# FPGA_Bank.net
KiCad netlist of a schematic drawn in Altium Designer
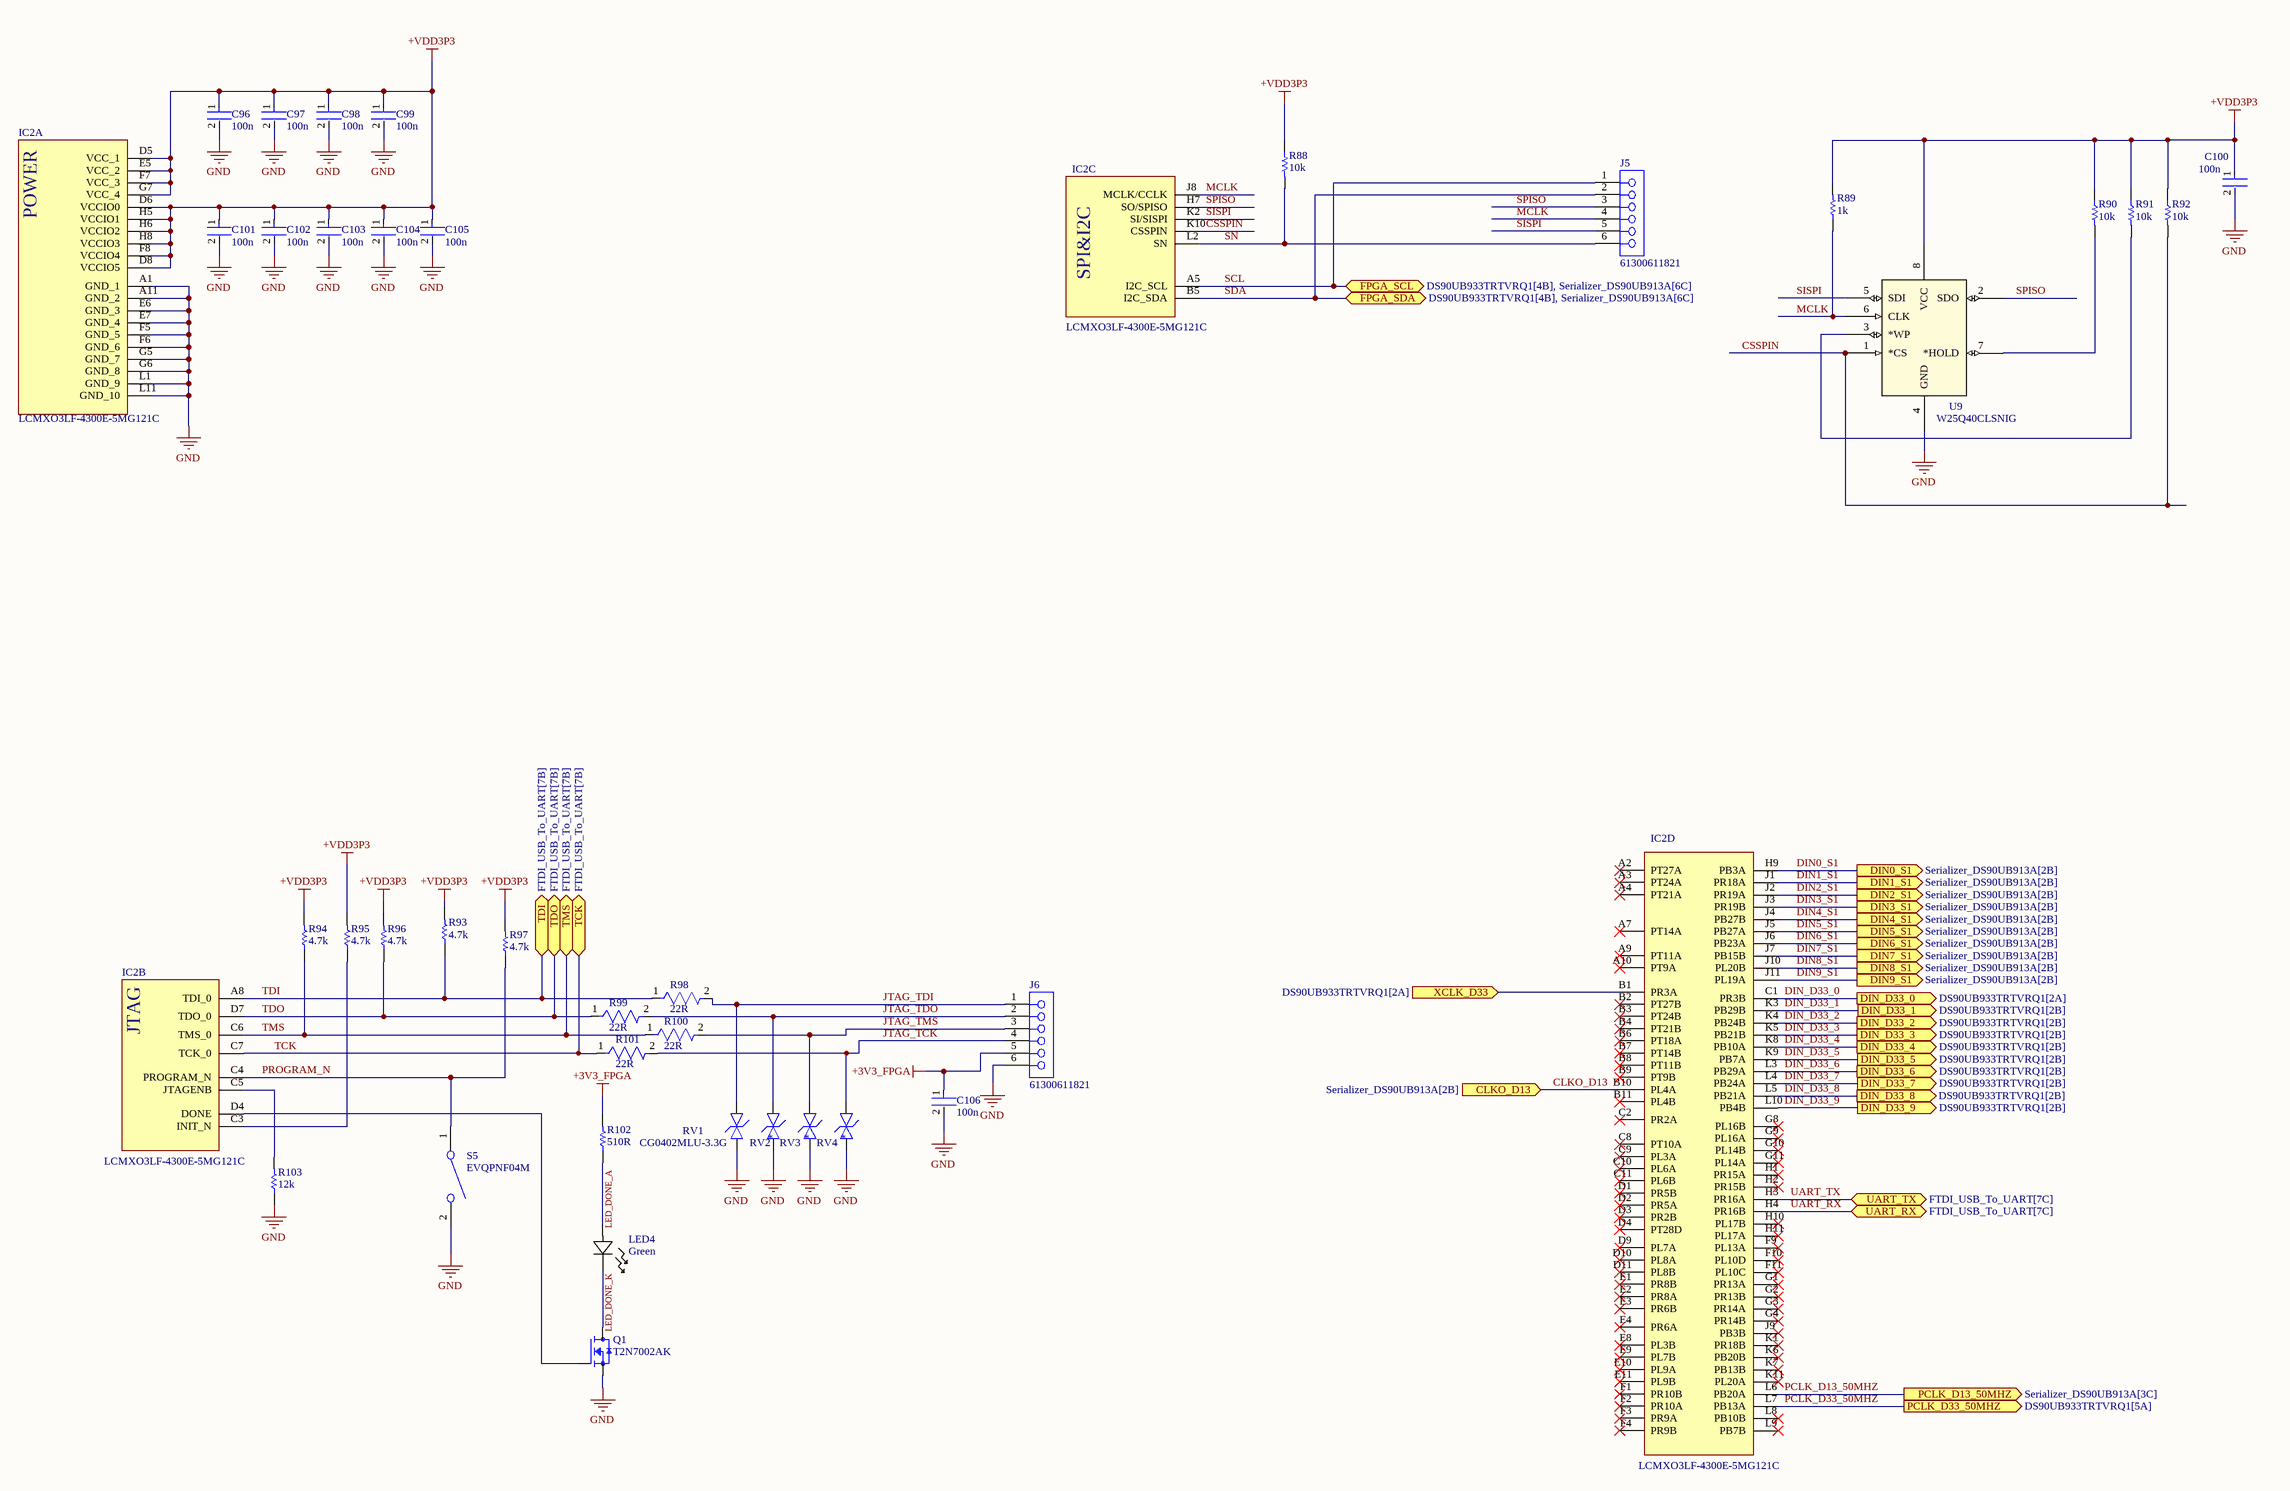
[diagram p0: FPGA_Bank.SchDoc]

(export (version "E")
  (design (tool "Eeschema 10.0.6"))
  (components
    (comp (ref "C96")
      (value "100n")
      (footprint "FP-CL278-IPC_C")
      (description "Cap Ceramic 100nF 25V X5R ±10% SMD 0402 +85°C Paper T/R")
      (fields (field (name "VOLTAGE") "25V") (field (name "TOLERANCE") "10%"))
      (libsource (lib "Altium Content Vault") (part "b4654b650e69147ec39a6b967a45e02"))
    )
    (comp (ref "C97")
      (value "100n")
      (footprint "FP-CL278-IPC_C")
      (description "Cap Ceramic 100nF 25V X5R ±10% SMD 0402 +85°C Paper T/R")
      (fields (field (name "VOLTAGE") "25V") (field (name "TOLERANCE") "10%"))
      (libsource (lib "Altium Content Vault") (part "b4654b650e69147ec39a6b967a45e02"))
    )
    (comp (ref "C98")
      (value "100n")
      (footprint "FP-CL278-IPC_C")
      (description "Cap Ceramic 100nF 25V X5R ±10% SMD 0402 +85°C Paper T/R")
      (fields (field (name "VOLTAGE") "25V") (field (name "TOLERANCE") "10%"))
      (libsource (lib "Altium Content Vault") (part "b4654b650e69147ec39a6b967a45e02"))
    )
    (comp (ref "C99")
      (value "100n")
      (footprint "FP-CL278-IPC_C")
      (description "Cap Ceramic 100nF 25V X5R ±10% SMD 0402 +85°C Paper T/R")
      (fields (field (name "VOLTAGE") "25V") (field (name "TOLERANCE") "10%"))
      (libsource (lib "Altium Content Vault") (part "b4654b650e69147ec39a6b967a45e02"))
    )
    (comp (ref "C100")
      (value "100n")
      (footprint "FP-CL278-IPC_C")
      (description "Cap Ceramic 100nF 25V X5R ±10% SMD 0402 +85°C Paper T/R")
      (fields (field (name "VOLTAGE") "25V") (field (name "TOLERANCE") "10%"))
      (libsource (lib "Altium Content Vault") (part "b4654b650e69147ec39a6b967a45e02"))
    )
    (comp (ref "C101")
      (value "100n")
      (footprint "FP-CL278-IPC_C")
      (description "Cap Ceramic 100nF 25V X5R ±10% SMD 0402 +85°C Paper T/R")
      (fields (field (name "VOLTAGE") "25V") (field (name "TOLERANCE") "10%"))
      (libsource (lib "Altium Content Vault") (part "b4654b650e69147ec39a6b967a45e02"))
    )
    (comp (ref "C102")
      (value "100n")
      (footprint "FP-CL278-IPC_C")
      (description "Cap Ceramic 100nF 25V X5R ±10% SMD 0402 +85°C Paper T/R")
      (fields (field (name "VOLTAGE") "25V") (field (name "TOLERANCE") "10%"))
      (libsource (lib "Altium Content Vault") (part "b4654b650e69147ec39a6b967a45e02"))
    )
    (comp (ref "C103")
      (value "100n")
      (footprint "FP-CL278-IPC_C")
      (description "Cap Ceramic 100nF 25V X5R ±10% SMD 0402 +85°C Paper T/R")
      (fields (field (name "VOLTAGE") "25V") (field (name "TOLERANCE") "10%"))
      (libsource (lib "Altium Content Vault") (part "b4654b650e69147ec39a6b967a45e02"))
    )
    (comp (ref "C104")
      (value "100n")
      (footprint "FP-CL278-IPC_C")
      (description "Cap Ceramic 100nF 25V X5R ±10% SMD 0402 +85°C Paper T/R")
      (fields (field (name "VOLTAGE") "25V") (field (name "TOLERANCE") "10%"))
      (libsource (lib "Altium Content Vault") (part "b4654b650e69147ec39a6b967a45e02"))
    )
    (comp (ref "C105")
      (value "100n")
      (footprint "FP-CL278-IPC_C")
      (description "Cap Ceramic 100nF 25V X5R ±10% SMD 0402 +85°C Paper T/R")
      (fields (field (name "VOLTAGE") "25V") (field (name "TOLERANCE") "10%"))
      (libsource (lib "Altium Content Vault") (part "b4654b650e69147ec39a6b967a45e02"))
    )
    (comp (ref "C106")
      (value "100n")
      (footprint "FP-CL278-IPC_C")
      (description "Cap Ceramic 100nF 25V X5R ±10% SMD 0402 +85°C Paper T/R")
      (fields (field (name "VOLTAGE") "25V") (field (name "TOLERANCE") "10%"))
      (libsource (lib "Altium Content Vault") (part "b4654b650e69147ec39a6b967a45e02"))
    )
    (comp (ref "IC2")
      (value "LCMXO3LF-4300E-5MG121C")
      (footprint "SerDes_Eval_Board_Footprints:CSFBGA-121_L6.0-W6.0-R11-C11-P0.50-TL")
      (description "FPGA IC")
      (fields (field (name "MOUSER PART NUMBER") "842-O3LF4300E5MG121C"))
      (libsource (lib "SerDes_Eval") (part "LCMXO3LF-4300E-5MG121C"))
    )
    (comp (ref "J5")
      (value "61300611821")
      (footprint "61300611821")
      (description "THT Vertical Socket Header WR-PHD, Pitch 2.54 mm, Single Row, 6 pins")
      (libsource (lib "Altium Content Vault") (part "Header_Female_1R_06P"))
    )
    (comp (ref "J6")
      (value "61300611821")
      (footprint "61300611821")
      (description "THT Vertical Socket Header WR-PHD, Pitch 2.54 mm, Single Row, 6 pins")
      (libsource (lib "Altium Content Vault") (part "Header_Female_1R_06P"))
    )
    (comp (ref "LED4")
      (value "Green")
      (footprint "LED_LTW-C193TS5_LTO")
      (description "No Description Available")
      (fields
        (field (name "MANUFACTURER_PART_NUMBER") "LTST-C191TGKT")
        (field (name "COPYRIGHT") "Copyright (C) 2025 Ultra Librarian. All rights reserved.")
      )
      (libsource (lib "SerDes_Eval") (part "LTST-C191TGKT"))
    )
    (comp (ref "Q1")
      (value "T2N7002AK")
      (footprint "SOT-23_TOS")
      (description "N-ch MOSFET, 60 V, 0.2 A, 3.9 Î©@10V, SOT-23(SOT23)")
      (fields (field (name "COPYRIGHT") "Copyright (C) 2025 Ultra Librarian. All rights reserved."))
      (libsource (lib "SerDes_Eval") (part "T2N7002AK"))
    )
    (comp (ref "R88")
      (value "10k")
      (footprint "RESC1005X40X25ML05T10")
      (fields (field (name "PART NUMBER") "CRCW040210K0FKEDHP") (field (name "MANUFACTURER") "Vishay Dale"))
      (libsource (lib "Altium Content Vault") (part "RES"))
    )
    (comp (ref "R89")
      (value "1k")
      (footprint "RESC1005X40X25NL05T05")
      (description "Chip Resistor, 1 KOhm, +/- 1%, 100 mW, -55 to 155 degC, 0402 (1005 Metric), RoHS, Tape and Reel")
      (fields (field (name "PARTNUMBER") "ERJ-2RKF1001X") (field (name "MANUFACTURER") "Basic Passives"))
      (libsource (lib "Altium Content Vault") (part "RES-2"))
    )
    (comp (ref "R90")
      (value "10k")
      (footprint "RESC1005X40X25ML05T10")
      (fields (field (name "PART NUMBER") "CRCW040210K0FKEDHP") (field (name "MANUFACTURER") "Vishay Dale"))
      (libsource (lib "Altium Content Vault") (part "RES"))
    )
    (comp (ref "R91")
      (value "10k")
      (footprint "RESC1005X40X25ML05T10")
      (fields (field (name "PART NUMBER") "CRCW040210K0FKEDHP") (field (name "MANUFACTURER") "Vishay Dale"))
      (libsource (lib "Altium Content Vault") (part "RES"))
    )
    (comp (ref "R92")
      (value "10k")
      (footprint "RESC1005X40X25ML05T10")
      (fields (field (name "PART NUMBER") "CRCW040210K0FKEDHP") (field (name "MANUFACTURER") "Vishay Dale"))
      (libsource (lib "Altium Content Vault") (part "RES"))
    )
    (comp (ref "R93")
      (value "4.7k")
      (footprint "RESC1005X40X25LL05T05")
      (description "Chip Resistor, 4.7 KOhm, +/- 1%, 0.1 W, -55 to 155 degC, 0402 (1005 Metric), RoHS, Tape and Reel")
      (fields (field (name "TOLERANCE") "1%") (field (name "PARTNUMBER") "ERJ-2RKF4701X"))
      (libsource (lib "Altium Content Vault") (part "RES-2"))
    )
    (comp (ref "R94")
      (value "4.7k")
      (footprint "RESC1005X40X25LL05T05")
      (description "Chip Resistor, 4.7 KOhm, +/- 1%, 0.1 W, -55 to 155 degC, 0402 (1005 Metric), RoHS, Tape and Reel")
      (fields (field (name "TOLERANCE") "1%") (field (name "PARTNUMBER") "ERJ-2RKF4701X"))
      (libsource (lib "Altium Content Vault") (part "RES-2"))
    )
    (comp (ref "R95")
      (value "4.7k")
      (footprint "RESC1005X40X25LL05T05")
      (description "Chip Resistor, 4.7 KOhm, +/- 1%, 0.1 W, -55 to 155 degC, 0402 (1005 Metric), RoHS, Tape and Reel")
      (fields (field (name "TOLERANCE") "1%") (field (name "PARTNUMBER") "ERJ-2RKF4701X"))
      (libsource (lib "Altium Content Vault") (part "RES-2"))
    )
    (comp (ref "R96")
      (value "4.7k")
      (footprint "RESC1005X40X25LL05T05")
      (description "Chip Resistor, 4.7 KOhm, +/- 1%, 0.1 W, -55 to 155 degC, 0402 (1005 Metric), RoHS, Tape and Reel")
      (fields (field (name "TOLERANCE") "1%") (field (name "PARTNUMBER") "ERJ-2RKF4701X"))
      (libsource (lib "Altium Content Vault") (part "RES-2"))
    )
    (comp (ref "R97")
      (value "4.7k")
      (footprint "RESC1005X40X25LL05T05")
      (description "Chip Resistor, 4.7 KOhm, +/- 1%, 0.1 W, -55 to 155 degC, 0402 (1005 Metric), RoHS, Tape and Reel")
      (fields (field (name "TOLERANCE") "1%") (field (name "PARTNUMBER") "ERJ-2RKF4701X"))
      (libsource (lib "Altium Content Vault") (part "RES-2"))
    )
    (comp (ref "R98")
      (value "22R")
      (footprint "FP-RC0402-0_4-MFG")
      (fields (field (name "TOLERANCE") "1%"))
      (libsource (lib "Altium Content Vault") (part "RC0402FR-0722RL"))
    )
    (comp (ref "R99")
      (value "22R")
      (footprint "FP-RC0402-0_4-MFG")
      (fields (field (name "TOLERANCE") "1%"))
      (libsource (lib "Altium Content Vault") (part "RC0402FR-0722RL"))
    )
    (comp (ref "R100")
      (value "22R")
      (footprint "FP-RC0402-0_4-MFG")
      (fields (field (name "TOLERANCE") "1%"))
      (libsource (lib "Altium Content Vault") (part "RC0402FR-0722RL"))
    )
    (comp (ref "R101")
      (value "22R")
      (footprint "FP-RC0402-0_4-MFG")
      (fields (field (name "TOLERANCE") "1%"))
      (libsource (lib "Altium Content Vault") (part "RC0402FR-0722RL"))
    )
    (comp (ref "R102")
      (value "510R")
      (footprint "RESC1005X40X25LL05T05")
      (fields (field (name "PART NUMBER") "CRCW0402510RFKED") (field (name "MANUFACTURER") "Vishay Dale"))
      (libsource (lib "Altium Content Vault") (part "RES"))
    )
    (comp (ref "R103")
      (value "12k")
      (footprint "RESC1005X40X25NL05T10")
      (fields (field (name "PART NUMBER") "RC0402FR-07100KL") (field (name "MANUFACTURER") "Yageo / Phycomp"))
      (libsource (lib "Altium Content Vault") (part "RES"))
    )
    (comp (ref "RV1")
      (value "CG0402MLU-3.3G")
      (footprint "SamacSys:VARC1005X41N")
      (description "Varistor")
      (fields (field (name "MOUSER PART NUMBER") "652-CG0402MLU-3.3G"))
      (libsource (lib "SerDes_Eval") (part "CG0402MLU-3.3G"))
    )
    (comp (ref "RV2")
      (value "*")
      (footprint "SamacSys:VARC1005X41N")
      (description "Varistor")
      (fields
        (field (name "MANUFACTURER_PART_NUMBER") "CG0402MLU-3.3G")
        (field (name "MOUSER PART NUMBER") "652-CG0402MLU-3.3G")
      )
      (libsource (lib "*") (part "CG0402MLU-3.3G"))
    )
    (comp (ref "RV3")
      (value "*")
      (footprint "SamacSys:VARC1005X41N")
      (description "Varistor")
      (fields
        (field (name "MANUFACTURER_PART_NUMBER") "CG0402MLU-3.3G")
        (field (name "MOUSER PART NUMBER") "652-CG0402MLU-3.3G")
      )
      (libsource (lib "*") (part "CG0402MLU-3.3G"))
    )
    (comp (ref "RV4")
      (value "*")
      (footprint "SamacSys:VARC1005X41N")
      (description "Varistor")
      (fields
        (field (name "MANUFACTURER_PART_NUMBER") "CG0402MLU-3.3G")
        (field (name "MOUSER PART NUMBER") "652-CG0402MLU-3.3G")
      )
      (libsource (lib "*") (part "CG0402MLU-3.3G"))
    )
    (comp (ref "S5")
      (value "EVQPNF04M")
      (footprint "SamacSys:EVQ5PN05K")
      (description "Switch")
      (libsource (lib "SerDes_Eval") (part "EVQPNF04M"))
    )
    (comp (ref "U9")
      (value "W25Q40CLSNIG")
      (footprint "WIN_SN-8_WIN")
      (description "No Description Available")
      (fields (field (name "COPYRIGHT") "Copyright (C) 2026 Ultra Librarian. All rights reserved."))
      (libsource (lib "SerDes_Eval") (part "W25Q40CLSNIG"))
    )
  )
  (nets
    (net (code "1") (name "+3V3_FPGA") (class "Default")
      (node (ref "C106") (pin "1") (pinfunction "1_1") (pintype "passive"))
      (node (ref "J6") (pin "5") (pinfunction "5_5") (pintype "passive"))
      (node (ref "R102") (pin "2") (pinfunction "2_2") (pintype "passive"))
    )
    (net (code "2") (name "+VDD3P3") (class "Default")
      (node (ref "C100") (pin "1") (pinfunction "1_1") (pintype "passive"))
      (node (ref "C101") (pin "1") (pinfunction "1_1") (pintype "passive"))
      (node (ref "C102") (pin "1") (pinfunction "1_1") (pintype "passive"))
      (node (ref "C103") (pin "1") (pinfunction "1_1") (pintype "passive"))
      (node (ref "C104") (pin "1") (pinfunction "1_1") (pintype "passive"))
      (node (ref "C105") (pin "1") (pinfunction "1_1") (pintype "passive"))
      (node (ref "C96") (pin "1") (pinfunction "1_1") (pintype "passive"))
      (node (ref "C97") (pin "1") (pinfunction "1_1") (pintype "passive"))
      (node (ref "C98") (pin "1") (pinfunction "1_1") (pintype "passive"))
      (node (ref "C99") (pin "1") (pinfunction "1_1") (pintype "passive"))
      (node (ref "IC2") (pin "D5") (pinfunction "VCC_1_D5") (pintype "passive"))
      (node (ref "IC2") (pin "D6") (pinfunction "VCCIO0_D6") (pintype "passive"))
      (node (ref "IC2") (pin "D8") (pinfunction "VCCIO5_D8") (pintype "passive"))
      (node (ref "IC2") (pin "E5") (pinfunction "VCC_2_E5") (pintype "passive"))
      (node (ref "IC2") (pin "F7") (pinfunction "VCC_3_F7") (pintype "passive"))
      (node (ref "IC2") (pin "F8") (pinfunction "VCCIO4_F8") (pintype "passive"))
      (node (ref "IC2") (pin "G7") (pinfunction "VCC_4_G7") (pintype "passive"))
      (node (ref "IC2") (pin "H5") (pinfunction "VCCIO1_H5") (pintype "passive"))
      (node (ref "IC2") (pin "H6") (pinfunction "VCCIO2_H6") (pintype "passive"))
      (node (ref "IC2") (pin "H8") (pinfunction "VCCIO3_H8") (pintype "passive"))
      (node (ref "R88") (pin "1") (pinfunction "1_1") (pintype "passive"))
      (node (ref "R89") (pin "2") (pinfunction "2_2") (pintype "passive"))
      (node (ref "R90") (pin "1") (pinfunction "1_1") (pintype "passive"))
      (node (ref "R91") (pin "1") (pinfunction "1_1") (pintype "passive"))
      (node (ref "R92") (pin "1") (pinfunction "1_1") (pintype "passive"))
      (node (ref "R93") (pin "2") (pinfunction "2_2") (pintype "passive"))
      (node (ref "R94") (pin "2") (pinfunction "2_2") (pintype "passive"))
      (node (ref "R95") (pin "2") (pinfunction "2_2") (pintype "passive"))
      (node (ref "R96") (pin "2") (pinfunction "2_2") (pintype "passive"))
      (node (ref "R97") (pin "2") (pinfunction "2_2") (pintype "passive"))
      (node (ref "U9") (pin "8") (pinfunction "VCC_8") (pintype "power_in"))
    )
    (net (code "3") (name "/CLKO_D13") (class "Default")
      (node (ref "IC2") (pin "B10") (pinfunction "PL4A_B10") (pintype "passive"))
    )
    (net (code "4") (name "/CSSPIN") (class "Default")
      (node (ref "IC2") (pin "K10") (pinfunction "CSSPIN_K10") (pintype "passive"))
      (node (ref "R92") (pin "2") (pinfunction "2_2") (pintype "passive"))
      (node (ref "U9") (pin "1") (pinfunction "*CS_1") (pintype "input"))
    )
    (net (code "5") (name "/DIN0_S1") (class "Default")
      (node (ref "IC2") (pin "H9") (pinfunction "PB3A_H9") (pintype "passive"))
    )
    (net (code "6") (name "/DIN1_S1") (class "Default")
      (node (ref "IC2") (pin "J1") (pinfunction "PR18A_J1") (pintype "passive"))
    )
    (net (code "7") (name "/DIN2_S1") (class "Default")
      (node (ref "IC2") (pin "J2") (pinfunction "PR19A_J2") (pintype "passive"))
    )
    (net (code "8") (name "/DIN3_S1") (class "Default")
      (node (ref "IC2") (pin "J3") (pinfunction "PR19B_J3") (pintype "passive"))
    )
    (net (code "9") (name "/DIN4_S1") (class "Default")
      (node (ref "IC2") (pin "J4") (pinfunction "PB27B_J4") (pintype "passive"))
    )
    (net (code "10") (name "/DIN5_S1") (class "Default")
      (node (ref "IC2") (pin "J5") (pinfunction "PB27A_J5") (pintype "passive"))
    )
    (net (code "11") (name "/DIN6_S1") (class "Default")
      (node (ref "IC2") (pin "J6") (pinfunction "PB23A_J6") (pintype "passive"))
    )
    (net (code "12") (name "/DIN7_S1") (class "Default")
      (node (ref "IC2") (pin "J7") (pinfunction "PB15B_J7") (pintype "passive"))
    )
    (net (code "13") (name "/DIN8_S1") (class "Default")
      (node (ref "IC2") (pin "J10") (pinfunction "PL20B_J10") (pintype "passive"))
    )
    (net (code "14") (name "/DIN9_S1") (class "Default")
      (node (ref "IC2") (pin "J11") (pinfunction "PL19A_J11") (pintype "passive"))
    )
    (net (code "15") (name "/DIN_D33_0") (class "Default")
      (node (ref "IC2") (pin "C1") (pinfunction "PR3B_C1") (pintype "passive"))
    )
    (net (code "16") (name "/DIN_D33_1") (class "Default")
      (node (ref "IC2") (pin "K3") (pinfunction "PB29B_K3") (pintype "passive"))
    )
    (net (code "17") (name "/DIN_D33_2") (class "Default")
      (node (ref "IC2") (pin "K4") (pinfunction "PB24B_K4") (pintype "passive"))
    )
    (net (code "18") (name "/DIN_D33_3") (class "Default")
      (node (ref "IC2") (pin "K5") (pinfunction "PB21B_K5") (pintype "passive"))
    )
    (net (code "19") (name "/DIN_D33_4") (class "Default")
      (node (ref "IC2") (pin "K8") (pinfunction "PB10A_K8") (pintype "passive"))
    )
    (net (code "20") (name "/DIN_D33_5") (class "Default")
      (node (ref "IC2") (pin "K9") (pinfunction "PB7A_K9") (pintype "passive"))
    )
    (net (code "21") (name "/DIN_D33_6") (class "Default")
      (node (ref "IC2") (pin "L3") (pinfunction "PB29A_L3") (pintype "passive"))
    )
    (net (code "22") (name "/DIN_D33_7") (class "Default")
      (node (ref "IC2") (pin "L4") (pinfunction "PB24A_L4") (pintype "passive"))
    )
    (net (code "23") (name "/DIN_D33_8") (class "Default")
      (node (ref "IC2") (pin "L5") (pinfunction "PB21A_L5") (pintype "passive"))
    )
    (net (code "24") (name "/DIN_D33_9") (class "Default")
      (node (ref "IC2") (pin "L10") (pinfunction "PB4B_L10") (pintype "passive"))
    )
    (net (code "25") (name "/JTAG_TCK") (class "Default")
      (node (ref "J6") (pin "4") (pinfunction "4_4") (pintype "passive"))
      (node (ref "R101") (pin "2") (pinfunction "2_2") (pintype "passive"))
      (node (ref "RV4") (pin "K") (pinfunction "K_K") (pintype "passive"))
    )
    (net (code "26") (name "/JTAG_TDI") (class "Default")
      (node (ref "J6") (pin "1") (pinfunction "1_1") (pintype "passive"))
      (node (ref "R98") (pin "2") (pinfunction "2_2") (pintype "passive"))
      (node (ref "RV1") (pin "K") (pinfunction "K_K") (pintype "passive"))
    )
    (net (code "27") (name "/JTAG_TDO") (class "Default")
      (node (ref "J6") (pin "2") (pinfunction "2_2") (pintype "passive"))
      (node (ref "R99") (pin "2") (pinfunction "2_2") (pintype "passive"))
      (node (ref "RV2") (pin "K") (pinfunction "K_K") (pintype "passive"))
    )
    (net (code "28") (name "/JTAG_TMS") (class "Default")
      (node (ref "J6") (pin "3") (pinfunction "3_3") (pintype "passive"))
      (node (ref "R100") (pin "2") (pinfunction "2_2") (pintype "passive"))
      (node (ref "RV3") (pin "K") (pinfunction "K_K") (pintype "passive"))
    )
    (net (code "29") (name "/LED_DONE_A") (class "Default")
      (node (ref "LED4") (pin "2") (pinfunction "2_2") (pintype "passive"))
      (node (ref "R102") (pin "1") (pinfunction "1_1") (pintype "passive"))
    )
    (net (code "30") (name "/LED_DONE_K") (class "Default")
      (node (ref "LED4") (pin "1") (pinfunction "1_1") (pintype "passive"))
      (node (ref "Q1") (pin "3") (pinfunction "D_3") (pintype "passive"))
    )
    (net (code "31") (name "/MCLK") (class "Default")
      (node (ref "IC2") (pin "J8") (pinfunction "MCLK/CCLK_J8") (pintype "passive"))
      (node (ref "J5") (pin "4") (pinfunction "4_4") (pintype "passive"))
      (node (ref "R89") (pin "1") (pinfunction "1_1") (pintype "passive"))
      (node (ref "U9") (pin "6") (pinfunction "CLK_6") (pintype "input"))
    )
    (net (code "32") (name "/PCLK_D13_50MHZ") (class "Default")
      (node (ref "IC2") (pin "L6") (pinfunction "PB20A_L6") (pintype "passive"))
    )
    (net (code "33") (name "/PCLK_D33_50MHZ") (class "Default")
      (node (ref "IC2") (pin "L7") (pinfunction "PB13A_L7") (pintype "passive"))
    )
    (net (code "34") (name "/PROGRAM_N") (class "Default")
      (node (ref "IC2") (pin "C4") (pinfunction "PROGRAM_N_C4") (pintype "passive"))
      (node (ref "R97") (pin "1") (pinfunction "1_1") (pintype "passive"))
      (node (ref "S5") (pin "1") (pinfunction "COM_1") (pintype "passive"))
    )
    (net (code "35") (name "/SCL") (class "Default")
      (node (ref "IC2") (pin "A5") (pinfunction "I2C_SCL_A5") (pintype "passive"))
      (node (ref "J5") (pin "1") (pinfunction "1_1") (pintype "passive"))
    )
    (net (code "36") (name "/SDA") (class "Default")
      (node (ref "IC2") (pin "B5") (pinfunction "I2C_SDA_B5") (pintype "passive"))
      (node (ref "J5") (pin "2") (pinfunction "2_2") (pintype "passive"))
    )
    (net (code "37") (name "/SISPI") (class "Default")
      (node (ref "IC2") (pin "K2") (pinfunction "SI/SISPI_K2") (pintype "passive"))
      (node (ref "J5") (pin "5") (pinfunction "5_5") (pintype "passive"))
      (node (ref "U9") (pin "5") (pinfunction "SDI_5") (pintype "bidirectional"))
    )
    (net (code "38") (name "/SN") (class "Default")
      (node (ref "IC2") (pin "L2") (pinfunction "SN_L2") (pintype "passive"))
      (node (ref "J5") (pin "6") (pinfunction "6_6") (pintype "passive"))
      (node (ref "R88") (pin "2") (pinfunction "2_2") (pintype "passive"))
    )
    (net (code "39") (name "/SPISO") (class "Default")
      (node (ref "IC2") (pin "H7") (pinfunction "SO/SPISO_H7") (pintype "passive"))
      (node (ref "J5") (pin "3") (pinfunction "3_3") (pintype "passive"))
      (node (ref "U9") (pin "2") (pinfunction "SDO_2") (pintype "bidirectional"))
    )
    (net (code "40") (name "/TCK") (class "Default")
      (node (ref "IC2") (pin "C7") (pinfunction "TCK_0_C7") (pintype "passive"))
      (node (ref "R101") (pin "1") (pinfunction "1_1") (pintype "passive"))
    )
    (net (code "41") (name "/TDI") (class "Default")
      (node (ref "IC2") (pin "A8") (pinfunction "TDI_0_A8") (pintype "passive"))
      (node (ref "R93") (pin "1") (pinfunction "1_1") (pintype "passive"))
      (node (ref "R98") (pin "1") (pinfunction "1_1") (pintype "passive"))
    )
    (net (code "42") (name "/TDO") (class "Default")
      (node (ref "IC2") (pin "D7") (pinfunction "TDO_0_D7") (pintype "passive"))
      (node (ref "R96") (pin "1") (pinfunction "1_1") (pintype "passive"))
      (node (ref "R99") (pin "1") (pinfunction "1_1") (pintype "passive"))
    )
    (net (code "43") (name "/TMS") (class "Default")
      (node (ref "IC2") (pin "C6") (pinfunction "TMS_0_C6") (pintype "passive"))
      (node (ref "R100") (pin "1") (pinfunction "1_1") (pintype "passive"))
      (node (ref "R94") (pin "1") (pinfunction "1_1") (pintype "passive"))
    )
    (net (code "44") (name "/UART_RX") (class "Default")
      (node (ref "IC2") (pin "H4") (pinfunction "PR16B_H4") (pintype "passive"))
    )
    (net (code "45") (name "/UART_TX") (class "Default")
      (node (ref "IC2") (pin "H3") (pinfunction "PR16A_H3") (pintype "passive"))
    )
    (net (code "46") (name "/XCLK_D33") (class "Default")
      (node (ref "IC2") (pin "B1") (pinfunction "PR3A_B1") (pintype "passive"))
    )
    (net (code "47") (name "GND") (class "Default")
      (node (ref "C100") (pin "2") (pinfunction "2_2") (pintype "passive"))
      (node (ref "C101") (pin "2") (pinfunction "2_2") (pintype "passive"))
      (node (ref "C102") (pin "2") (pinfunction "2_2") (pintype "passive"))
      (node (ref "C103") (pin "2") (pinfunction "2_2") (pintype "passive"))
      (node (ref "C104") (pin "2") (pinfunction "2_2") (pintype "passive"))
      (node (ref "C105") (pin "2") (pinfunction "2_2") (pintype "passive"))
      (node (ref "C106") (pin "2") (pinfunction "2_2") (pintype "passive"))
      (node (ref "C96") (pin "2") (pinfunction "2_2") (pintype "passive"))
      (node (ref "C97") (pin "2") (pinfunction "2_2") (pintype "passive"))
      (node (ref "C98") (pin "2") (pinfunction "2_2") (pintype "passive"))
      (node (ref "C99") (pin "2") (pinfunction "2_2") (pintype "passive"))
      (node (ref "IC2") (pin "A1") (pinfunction "GND_1_A1") (pintype "passive"))
      (node (ref "IC2") (pin "A11") (pinfunction "GND_2_A11") (pintype "passive"))
      (node (ref "IC2") (pin "E6") (pinfunction "GND_3_E6") (pintype "passive"))
      (node (ref "IC2") (pin "E7") (pinfunction "GND_4_E7") (pintype "passive"))
      (node (ref "IC2") (pin "F5") (pinfunction "GND_5_F5") (pintype "passive"))
      (node (ref "IC2") (pin "F6") (pinfunction "GND_6_F6") (pintype "passive"))
      (node (ref "IC2") (pin "G5") (pinfunction "GND_7_G5") (pintype "passive"))
      (node (ref "IC2") (pin "G6") (pinfunction "GND_8_G6") (pintype "passive"))
      (node (ref "IC2") (pin "L1") (pinfunction "GND_9_L1") (pintype "passive"))
      (node (ref "IC2") (pin "L11") (pinfunction "GND_10_L11") (pintype "passive"))
      (node (ref "J6") (pin "6") (pinfunction "6_6") (pintype "passive"))
      (node (ref "Q1") (pin "2") (pinfunction "S_2") (pintype "passive"))
      (node (ref "R103") (pin "1") (pinfunction "1_1") (pintype "passive"))
      (node (ref "RV1") (pin "A") (pinfunction "A_A") (pintype "passive"))
      (node (ref "RV2") (pin "A") (pinfunction "A_A") (pintype "passive"))
      (node (ref "RV3") (pin "A") (pinfunction "A_A") (pintype "passive"))
      (node (ref "RV4") (pin "A") (pinfunction "A_A") (pintype "passive"))
      (node (ref "S5") (pin "2") (pinfunction "NO_2") (pintype "passive"))
      (node (ref "U9") (pin "4") (pinfunction "GND_4") (pintype "power_in"))
    )
    (net (code "48") (name "Net-(IC2B-DONE)") (class "Default")
      (node (ref "IC2") (pin "D4") (pinfunction "DONE_D4") (pintype "passive"))
      (node (ref "Q1") (pin "1") (pinfunction "G_1") (pintype "passive"))
    )
    (net (code "49") (name "Net-(IC2B-INIT_N)") (class "Default")
      (node (ref "IC2") (pin "C3") (pinfunction "INIT_N_C3") (pintype "passive"))
      (node (ref "R95") (pin "1") (pinfunction "1_1") (pintype "passive"))
    )
    (net (code "50") (name "Net-(IC2B-JTAGENB)") (class "Default")
      (node (ref "IC2") (pin "C5") (pinfunction "JTAGENB_C5") (pintype "passive"))
      (node (ref "R103") (pin "2") (pinfunction "2_2") (pintype "passive"))
    )
    (net (code "51") (name "Net-(U9-*HOLD)") (class "Default")
      (node (ref "R90") (pin "2") (pinfunction "2_2") (pintype "passive"))
      (node (ref "U9") (pin "7") (pinfunction "*HOLD_7") (pintype "bidirectional"))
    )
    (net (code "52") (name "Net-(U9-*WP)") (class "Default")
      (node (ref "R91") (pin "2") (pinfunction "2_2") (pintype "passive"))
      (node (ref "U9") (pin "3") (pinfunction "*WP_3") (pintype "bidirectional"))
    )
    (net (code "53") (name "unconnected-(IC2D-PB3B-PadJ9)") (class "Default")
      (node (ref "IC2") (pin "J9") (pinfunction "PB3B_J9") (pintype "passive+no_connect"))
    )
    (net (code "54") (name "unconnected-(IC2D-PB7B-PadL9)") (class "Default")
      (node (ref "IC2") (pin "L9") (pinfunction "PB7B_L9") (pintype "passive+no_connect"))
    )
    (net (code "55") (name "unconnected-(IC2D-PB10B-PadL8)") (class "Default")
      (node (ref "IC2") (pin "L8") (pinfunction "PB10B_L8") (pintype "passive+no_connect"))
    )
    (net (code "56") (name "unconnected-(IC2D-PB13B-PadK7)") (class "Default")
      (node (ref "IC2") (pin "K7") (pinfunction "PB13B_K7") (pintype "passive+no_connect"))
    )
    (net (code "57") (name "unconnected-(IC2D-PB20B-PadK6)") (class "Default")
      (node (ref "IC2") (pin "K6") (pinfunction "PB20B_K6") (pintype "passive+no_connect"))
    )
    (net (code "58") (name "unconnected-(IC2D-PL3A-PadC9)") (class "Default")
      (node (ref "IC2") (pin "C9") (pinfunction "PL3A_C9") (pintype "passive+no_connect"))
    )
    (net (code "59") (name "unconnected-(IC2D-PL3B-PadE8)") (class "Default")
      (node (ref "IC2") (pin "E8") (pinfunction "PL3B_E8") (pintype "passive+no_connect"))
    )
    (net (code "60") (name "unconnected-(IC2D-PL4B-PadB11)") (class "Default")
      (node (ref "IC2") (pin "B11") (pinfunction "PL4B_B11") (pintype "passive+no_connect"))
    )
    (net (code "61") (name "unconnected-(IC2D-PL6A-PadC10)") (class "Default")
      (node (ref "IC2") (pin "C10") (pinfunction "PL6A_C10") (pintype "passive+no_connect"))
    )
    (net (code "62") (name "unconnected-(IC2D-PL6B-PadC11)") (class "Default")
      (node (ref "IC2") (pin "C11") (pinfunction "PL6B_C11") (pintype "passive+no_connect"))
    )
    (net (code "63") (name "unconnected-(IC2D-PL7A-PadD9)") (class "Default")
      (node (ref "IC2") (pin "D9") (pinfunction "PL7A_D9") (pintype "passive+no_connect"))
    )
    (net (code "64") (name "unconnected-(IC2D-PL7B-PadE9)") (class "Default")
      (node (ref "IC2") (pin "E9") (pinfunction "PL7B_E9") (pintype "passive+no_connect"))
    )
    (net (code "65") (name "unconnected-(IC2D-PL8A-PadD10)") (class "Default")
      (node (ref "IC2") (pin "D10") (pinfunction "PL8A_D10") (pintype "passive+no_connect"))
    )
    (net (code "66") (name "unconnected-(IC2D-PL8B-PadD11)") (class "Default")
      (node (ref "IC2") (pin "D11") (pinfunction "PL8B_D11") (pintype "passive+no_connect"))
    )
    (net (code "67") (name "unconnected-(IC2D-PL9A-PadE10)") (class "Default")
      (node (ref "IC2") (pin "E10") (pinfunction "PL9A_E10") (pintype "passive+no_connect"))
    )
    (net (code "68") (name "unconnected-(IC2D-PL9B-PadE11)") (class "Default")
      (node (ref "IC2") (pin "E11") (pinfunction "PL9B_E11") (pintype "passive+no_connect"))
    )
    (net (code "69") (name "unconnected-(IC2D-PL10C-PadF11)") (class "Default")
      (node (ref "IC2") (pin "F11") (pinfunction "PL10C_F11") (pintype "passive+no_connect"))
    )
    (net (code "70") (name "unconnected-(IC2D-PL10D-PadF10)") (class "Default")
      (node (ref "IC2") (pin "F10") (pinfunction "PL10D_F10") (pintype "passive+no_connect"))
    )
    (net (code "71") (name "unconnected-(IC2D-PL13A-PadF9)") (class "Default")
      (node (ref "IC2") (pin "F9") (pinfunction "PL13A_F9") (pintype "passive+no_connect"))
    )
    (net (code "72") (name "unconnected-(IC2D-PL14A-PadG11)") (class "Default")
      (node (ref "IC2") (pin "G11") (pinfunction "PL14A_G11") (pintype "passive+no_connect"))
    )
    (net (code "73") (name "unconnected-(IC2D-PL14B-PadG10)") (class "Default")
      (node (ref "IC2") (pin "G10") (pinfunction "PL14B_G10") (pintype "passive+no_connect"))
    )
    (net (code "74") (name "unconnected-(IC2D-PL16A-PadG9)") (class "Default")
      (node (ref "IC2") (pin "G9") (pinfunction "PL16A_G9") (pintype "passive+no_connect"))
    )
    (net (code "75") (name "unconnected-(IC2D-PL16B-PadG8)") (class "Default")
      (node (ref "IC2") (pin "G8") (pinfunction "PL16B_G8") (pintype "passive+no_connect"))
    )
    (net (code "76") (name "unconnected-(IC2D-PL17A-PadH11)") (class "Default")
      (node (ref "IC2") (pin "H11") (pinfunction "PL17A_H11") (pintype "passive+no_connect"))
    )
    (net (code "77") (name "unconnected-(IC2D-PL17B-PadH10)") (class "Default")
      (node (ref "IC2") (pin "H10") (pinfunction "PL17B_H10") (pintype "passive+no_connect"))
    )
    (net (code "78") (name "unconnected-(IC2D-PL20A-PadK11)") (class "Default")
      (node (ref "IC2") (pin "K11") (pinfunction "PL20A_K11") (pintype "passive+no_connect"))
    )
    (net (code "79") (name "unconnected-(IC2D-PR2A-PadC2)") (class "Default")
      (node (ref "IC2") (pin "C2") (pinfunction "PR2A_C2") (pintype "passive+no_connect"))
    )
    (net (code "80") (name "unconnected-(IC2D-PR2B-PadD3)") (class "Default")
      (node (ref "IC2") (pin "D3") (pinfunction "PR2B_D3") (pintype "passive+no_connect"))
    )
    (net (code "81") (name "unconnected-(IC2D-PR5A-PadD2)") (class "Default")
      (node (ref "IC2") (pin "D2") (pinfunction "PR5A_D2") (pintype "passive+no_connect"))
    )
    (net (code "82") (name "unconnected-(IC2D-PR5B-PadD1)") (class "Default")
      (node (ref "IC2") (pin "D1") (pinfunction "PR5B_D1") (pintype "passive+no_connect"))
    )
    (net (code "83") (name "unconnected-(IC2D-PR6A-PadE4)") (class "Default")
      (node (ref "IC2") (pin "E4") (pinfunction "PR6A_E4") (pintype "passive+no_connect"))
    )
    (net (code "84") (name "unconnected-(IC2D-PR6B-PadE3)") (class "Default")
      (node (ref "IC2") (pin "E3") (pinfunction "PR6B_E3") (pintype "passive+no_connect"))
    )
    (net (code "85") (name "unconnected-(IC2D-PR8A-PadE2)") (class "Default")
      (node (ref "IC2") (pin "E2") (pinfunction "PR8A_E2") (pintype "passive+no_connect"))
    )
    (net (code "86") (name "unconnected-(IC2D-PR8B-PadE1)") (class "Default")
      (node (ref "IC2") (pin "E1") (pinfunction "PR8B_E1") (pintype "passive+no_connect"))
    )
    (net (code "87") (name "unconnected-(IC2D-PR9A-PadF3)") (class "Default")
      (node (ref "IC2") (pin "F3") (pinfunction "PR9A_F3") (pintype "passive+no_connect"))
    )
    (net (code "88") (name "unconnected-(IC2D-PR9B-PadF4)") (class "Default")
      (node (ref "IC2") (pin "F4") (pinfunction "PR9B_F4") (pintype "passive+no_connect"))
    )
    (net (code "89") (name "unconnected-(IC2D-PR10A-PadF2)") (class "Default")
      (node (ref "IC2") (pin "F2") (pinfunction "PR10A_F2") (pintype "passive+no_connect"))
    )
    (net (code "90") (name "unconnected-(IC2D-PR10B-PadF1)") (class "Default")
      (node (ref "IC2") (pin "F1") (pinfunction "PR10B_F1") (pintype "passive+no_connect"))
    )
    (net (code "91") (name "unconnected-(IC2D-PR13A-PadG1)") (class "Default")
      (node (ref "IC2") (pin "G1") (pinfunction "PR13A_G1") (pintype "passive+no_connect"))
    )
    (net (code "92") (name "unconnected-(IC2D-PR13B-PadG2)") (class "Default")
      (node (ref "IC2") (pin "G2") (pinfunction "PR13B_G2") (pintype "passive+no_connect"))
    )
    (net (code "93") (name "unconnected-(IC2D-PR14A-PadG3)") (class "Default")
      (node (ref "IC2") (pin "G3") (pinfunction "PR14A_G3") (pintype "passive+no_connect"))
    )
    (net (code "94") (name "unconnected-(IC2D-PR14B-PadG4)") (class "Default")
      (node (ref "IC2") (pin "G4") (pinfunction "PR14B_G4") (pintype "passive+no_connect"))
    )
    (net (code "95") (name "unconnected-(IC2D-PR15A-PadH1)") (class "Default")
      (node (ref "IC2") (pin "H1") (pinfunction "PR15A_H1") (pintype "passive+no_connect"))
    )
    (net (code "96") (name "unconnected-(IC2D-PR15B-PadH2)") (class "Default")
      (node (ref "IC2") (pin "H2") (pinfunction "PR15B_H2") (pintype "passive+no_connect"))
    )
    (net (code "97") (name "unconnected-(IC2D-PR18B-PadK1)") (class "Default")
      (node (ref "IC2") (pin "K1") (pinfunction "PR18B_K1") (pintype "passive+no_connect"))
    )
    (net (code "98") (name "unconnected-(IC2D-PT9A-PadA10)") (class "Default")
      (node (ref "IC2") (pin "A10") (pinfunction "PT9A_A10") (pintype "passive+no_connect"))
    )
    (net (code "99") (name "unconnected-(IC2D-PT9B-PadB9)") (class "Default")
      (node (ref "IC2") (pin "B9") (pinfunction "PT9B_B9") (pintype "passive+no_connect"))
    )
    (net (code "100") (name "unconnected-(IC2D-PT10A-PadC8)") (class "Default")
      (node (ref "IC2") (pin "C8") (pinfunction "PT10A_C8") (pintype "passive+no_connect"))
    )
    (net (code "101") (name "unconnected-(IC2D-PT11A-PadA9)") (class "Default")
      (node (ref "IC2") (pin "A9") (pinfunction "PT11A_A9") (pintype "passive+no_connect"))
    )
    (net (code "102") (name "unconnected-(IC2D-PT11B-PadB8)") (class "Default")
      (node (ref "IC2") (pin "B8") (pinfunction "PT11B_B8") (pintype "passive+no_connect"))
    )
    (net (code "103") (name "unconnected-(IC2D-PT14A-PadA7)") (class "Default")
      (node (ref "IC2") (pin "A7") (pinfunction "PT14A_A7") (pintype "passive+no_connect"))
    )
    (net (code "104") (name "unconnected-(IC2D-PT14B-PadB7)") (class "Default")
      (node (ref "IC2") (pin "B7") (pinfunction "PT14B_B7") (pintype "passive+no_connect"))
    )
    (net (code "105") (name "unconnected-(IC2D-PT18A-PadB6)") (class "Default")
      (node (ref "IC2") (pin "B6") (pinfunction "PT18A_B6") (pintype "passive+no_connect"))
    )
    (net (code "106") (name "unconnected-(IC2D-PT21A-PadA4)") (class "Default")
      (node (ref "IC2") (pin "A4") (pinfunction "PT21A_A4") (pintype "passive+no_connect"))
    )
    (net (code "107") (name "unconnected-(IC2D-PT21B-PadB4)") (class "Default")
      (node (ref "IC2") (pin "B4") (pinfunction "PT21B_B4") (pintype "passive+no_connect"))
    )
    (net (code "108") (name "unconnected-(IC2D-PT24A-PadA3)") (class "Default")
      (node (ref "IC2") (pin "A3") (pinfunction "PT24A_A3") (pintype "passive+no_connect"))
    )
    (net (code "109") (name "unconnected-(IC2D-PT24B-PadB3)") (class "Default")
      (node (ref "IC2") (pin "B3") (pinfunction "PT24B_B3") (pintype "passive+no_connect"))
    )
    (net (code "110") (name "unconnected-(IC2D-PT27A-PadA2)") (class "Default")
      (node (ref "IC2") (pin "A2") (pinfunction "PT27A_A2") (pintype "passive+no_connect"))
    )
    (net (code "111") (name "unconnected-(IC2D-PT27B-PadB2)") (class "Default")
      (node (ref "IC2") (pin "B2") (pinfunction "PT27B_B2") (pintype "passive+no_connect"))
    )
    (net (code "112") (name "unconnected-(IC2D-PT28D-PadD4)") (class "Default")
      (node (ref "IC2") (pin "D4") (pinfunction "PT28D_D4") (pintype "passive+no_connect"))
    )
  )
)
